# Logic_Level_Bidirectional.net
KiCad netlist of a schematic drawn in EAGLE
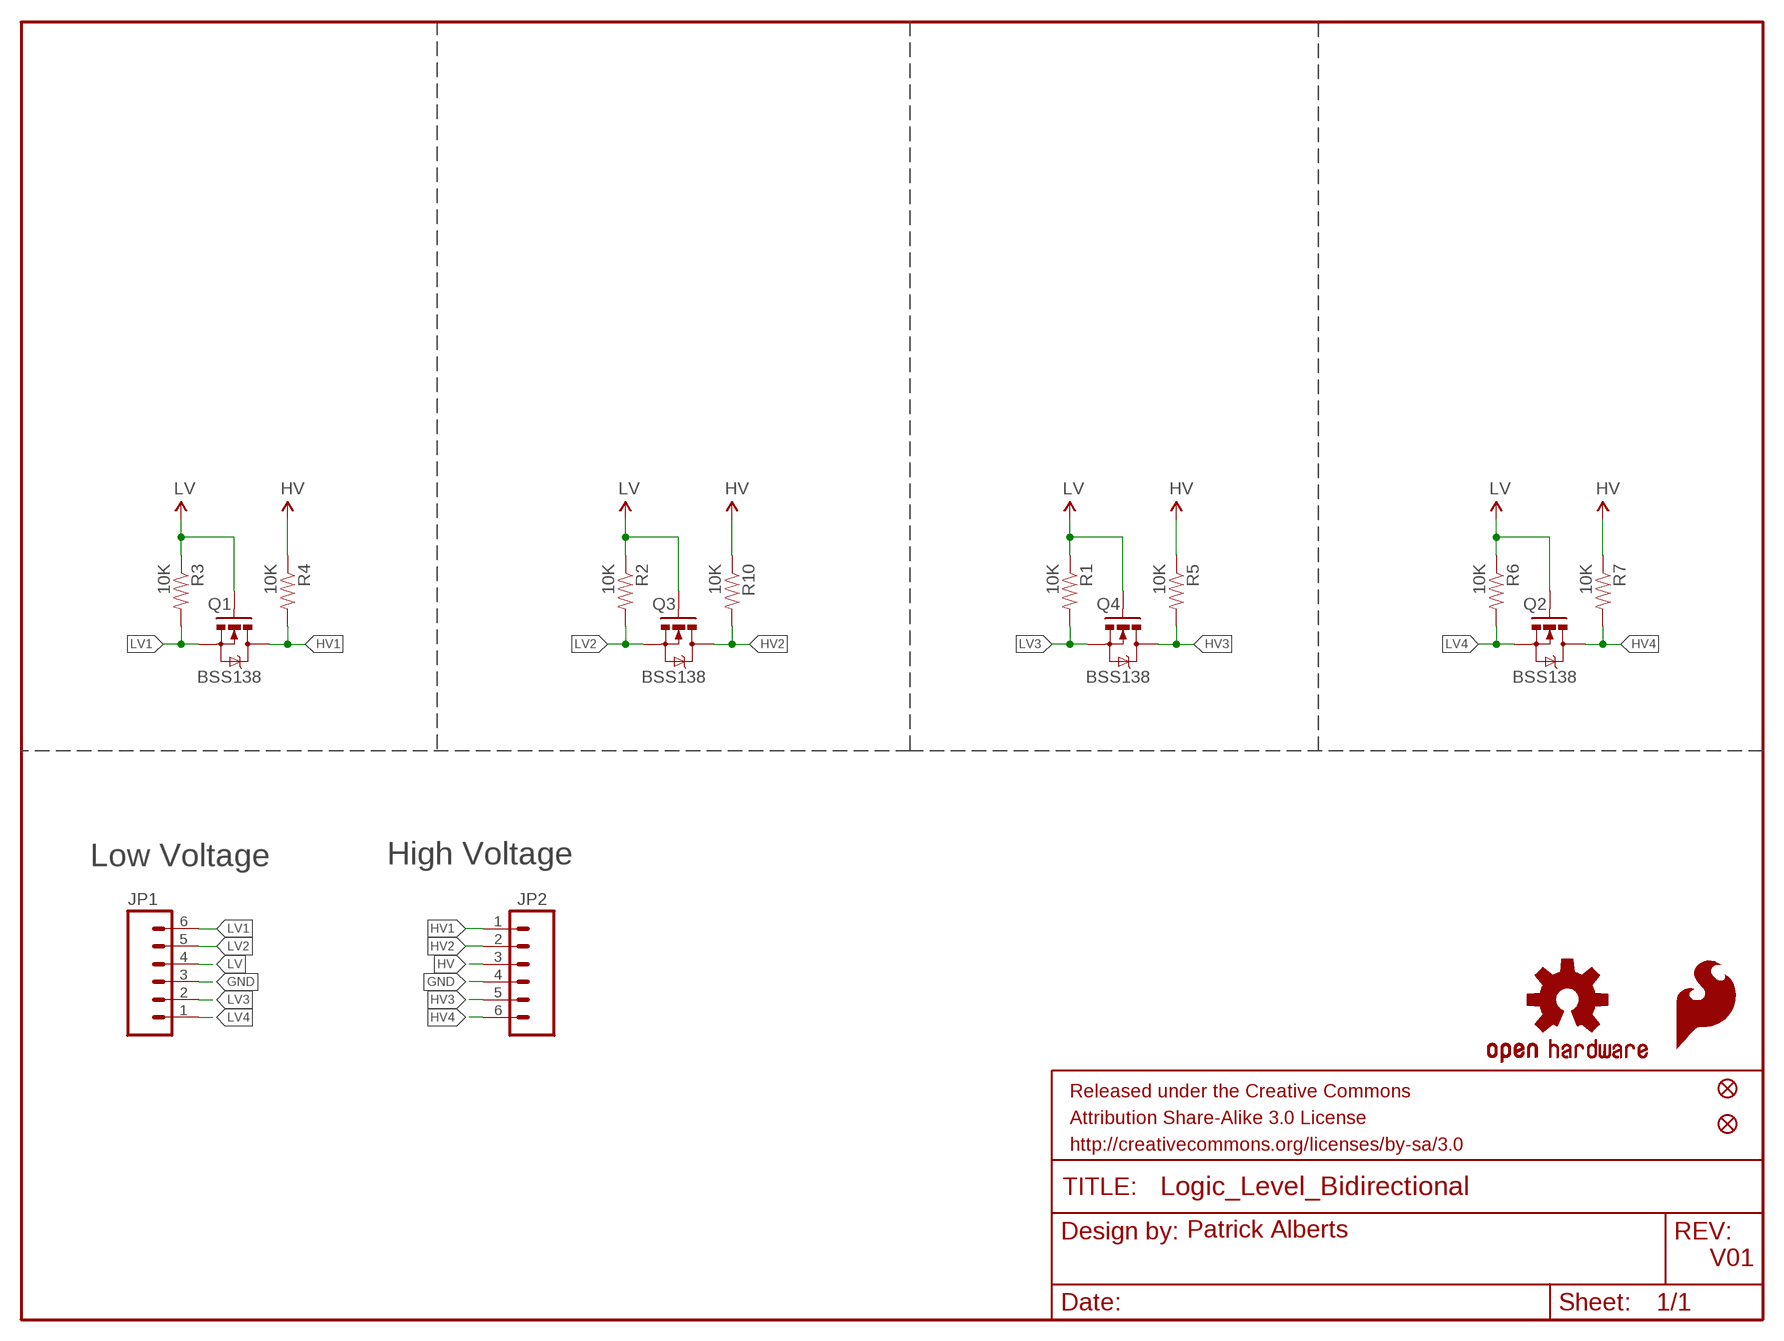
[diagram p0: schematic, sheet 1]

(export (version "E")
  (design (tool "Eeschema 10.0.6"))
  (components
    (comp (ref "JP1")
      (value "M06SIP")
      (footprint "eagle-import:1X06")
      (libsource (lib "eagle-import") (part "M06SIP"))
    )
    (comp (ref "JP2")
      (value "M06SIP")
      (footprint "eagle-import:1X06")
      (libsource (lib "eagle-import") (part "M06SIP"))
    )
    (comp (ref "JP3")
      (value "FIDUCIALUFIDUCIAL")
      (footprint "eagle-import:MICRO-FIDUCIAL")
      (libsource (lib "eagle-import") (part "FIDUCIALUFIDUCIAL"))
    )
    (comp (ref "JP4")
      (value "FIDUCIALUFIDUCIAL")
      (footprint "eagle-import:MICRO-FIDUCIAL")
      (libsource (lib "eagle-import") (part "FIDUCIALUFIDUCIAL"))
    )
    (comp (ref "LOGO1")
      (value "SFE_LOGO_FLAME.1_INCH")
      (footprint "eagle-import:SFE_LOGO_FLAME_.1")
      (libsource (lib "eagle-import") (part "SFE_LOGO_FLAME.1_INCH"))
    )
    (comp (ref "LOGO2")
      (value "OSHW-LOGOS")
      (footprint "eagle-import:OSHW-LOGO-S")
      (libsource (lib "eagle-import") (part "OSHW-LOGOS"))
    )
    (comp (ref "Q1")
      (value "BSS138")
      (footprint "eagle-import:SOT23-3")
      (libsource (lib "eagle-import") (part "MOSFET-NCHANNELSMD"))
    )
    (comp (ref "Q2")
      (value "BSS138")
      (footprint "eagle-import:SOT23-3")
      (libsource (lib "eagle-import") (part "MOSFET-NCHANNELSMD"))
    )
    (comp (ref "Q3")
      (value "BSS138")
      (footprint "eagle-import:SOT23-3")
      (libsource (lib "eagle-import") (part "MOSFET-NCHANNELSMD"))
    )
    (comp (ref "Q4")
      (value "BSS138")
      (footprint "eagle-import:SOT23-3")
      (libsource (lib "eagle-import") (part "MOSFET-NCHANNELSMD"))
    )
    (comp (ref "R1")
      (value "10K")
      (footprint "eagle-import:0603-RES")
      (libsource (lib "eagle-import") (part "RESISTOR0603-RES"))
    )
    (comp (ref "R2")
      (value "10K")
      (footprint "eagle-import:0603-RES")
      (libsource (lib "eagle-import") (part "RESISTOR0603-RES"))
    )
    (comp (ref "R3")
      (value "10K")
      (footprint "eagle-import:0603-RES")
      (libsource (lib "eagle-import") (part "RESISTOR0603-RES"))
    )
    (comp (ref "R4")
      (value "10K")
      (footprint "eagle-import:0603-RES")
      (libsource (lib "eagle-import") (part "RESISTOR0603-RES"))
    )
    (comp (ref "R5")
      (value "10K")
      (footprint "eagle-import:0603-RES")
      (libsource (lib "eagle-import") (part "RESISTOR0603-RES"))
    )
    (comp (ref "R6")
      (value "10K")
      (footprint "eagle-import:0603-RES")
      (libsource (lib "eagle-import") (part "RESISTOR0603-RES"))
    )
    (comp (ref "R7")
      (value "10K")
      (footprint "eagle-import:0603-RES")
      (libsource (lib "eagle-import") (part "RESISTOR0603-RES"))
    )
    (comp (ref "R10")
      (value "10K")
      (footprint "eagle-import:0603-RES")
      (libsource (lib "eagle-import") (part "RESISTOR0603-RES"))
    )
  )
  (nets
    (net (code "1") (name "GND") (class "Default")
      (node (ref "JP1") (pin "3") (pinfunction "3_3") (pintype "passive"))
      (node (ref "JP2") (pin "4") (pinfunction "4_4") (pintype "passive"))
    )
    (net (code "2") (name "HV") (class "Default")
      (node (ref "JP2") (pin "3") (pinfunction "3_3") (pintype "passive"))
      (node (ref "R10") (pin "1") (pinfunction "1_1") (pintype "passive"))
      (node (ref "R4") (pin "1") (pinfunction "1_1") (pintype "passive"))
      (node (ref "R5") (pin "1") (pinfunction "1_1") (pintype "passive"))
      (node (ref "R7") (pin "1") (pinfunction "1_1") (pintype "passive"))
    )
    (net (code "3") (name "HV1") (class "Default")
      (node (ref "JP2") (pin "1") (pinfunction "1_1") (pintype "passive"))
      (node (ref "Q1") (pin "3") (pinfunction "D_3") (pintype "passive"))
      (node (ref "R4") (pin "2") (pinfunction "2_2") (pintype "passive"))
    )
    (net (code "4") (name "HV2") (class "Default")
      (node (ref "JP2") (pin "2") (pinfunction "2_2") (pintype "passive"))
      (node (ref "Q3") (pin "3") (pinfunction "D_3") (pintype "passive"))
      (node (ref "R10") (pin "2") (pinfunction "2_2") (pintype "passive"))
    )
    (net (code "5") (name "HV3") (class "Default")
      (node (ref "JP2") (pin "5") (pinfunction "5_5") (pintype "passive"))
      (node (ref "Q4") (pin "3") (pinfunction "D_3") (pintype "passive"))
      (node (ref "R5") (pin "2") (pinfunction "2_2") (pintype "passive"))
    )
    (net (code "6") (name "HV4") (class "Default")
      (node (ref "JP2") (pin "6") (pinfunction "6_6") (pintype "passive"))
      (node (ref "Q2") (pin "3") (pinfunction "D_3") (pintype "passive"))
      (node (ref "R7") (pin "2") (pinfunction "2_2") (pintype "passive"))
    )
    (net (code "7") (name "LV") (class "Default")
      (node (ref "JP1") (pin "4") (pinfunction "4_4") (pintype "passive"))
      (node (ref "Q1") (pin "1") (pinfunction "G_1") (pintype "passive"))
      (node (ref "Q2") (pin "1") (pinfunction "G_1") (pintype "passive"))
      (node (ref "Q3") (pin "1") (pinfunction "G_1") (pintype "passive"))
      (node (ref "Q4") (pin "1") (pinfunction "G_1") (pintype "passive"))
      (node (ref "R1") (pin "1") (pinfunction "1_1") (pintype "passive"))
      (node (ref "R2") (pin "1") (pinfunction "1_1") (pintype "passive"))
      (node (ref "R3") (pin "1") (pinfunction "1_1") (pintype "passive"))
      (node (ref "R6") (pin "1") (pinfunction "1_1") (pintype "passive"))
    )
    (net (code "8") (name "LV1") (class "Default")
      (node (ref "JP1") (pin "6") (pinfunction "6_6") (pintype "passive"))
      (node (ref "Q1") (pin "2") (pinfunction "S_2") (pintype "passive"))
      (node (ref "R3") (pin "2") (pinfunction "2_2") (pintype "passive"))
    )
    (net (code "9") (name "LV2") (class "Default")
      (node (ref "JP1") (pin "5") (pinfunction "5_5") (pintype "passive"))
      (node (ref "Q3") (pin "2") (pinfunction "S_2") (pintype "passive"))
      (node (ref "R2") (pin "2") (pinfunction "2_2") (pintype "passive"))
    )
    (net (code "10") (name "LV3") (class "Default")
      (node (ref "JP1") (pin "2") (pinfunction "2_2") (pintype "passive"))
      (node (ref "Q4") (pin "2") (pinfunction "S_2") (pintype "passive"))
      (node (ref "R1") (pin "2") (pinfunction "2_2") (pintype "passive"))
    )
    (net (code "11") (name "LV4") (class "Default")
      (node (ref "JP1") (pin "1") (pinfunction "1_1") (pintype "passive"))
      (node (ref "Q2") (pin "2") (pinfunction "S_2") (pintype "passive"))
      (node (ref "R6") (pin "2") (pinfunction "2_2") (pintype "passive"))
    )
  )
)
